# scheda_progetto_ver_4_2.net
KiCad netlist of a schematic drawn in EAGLE
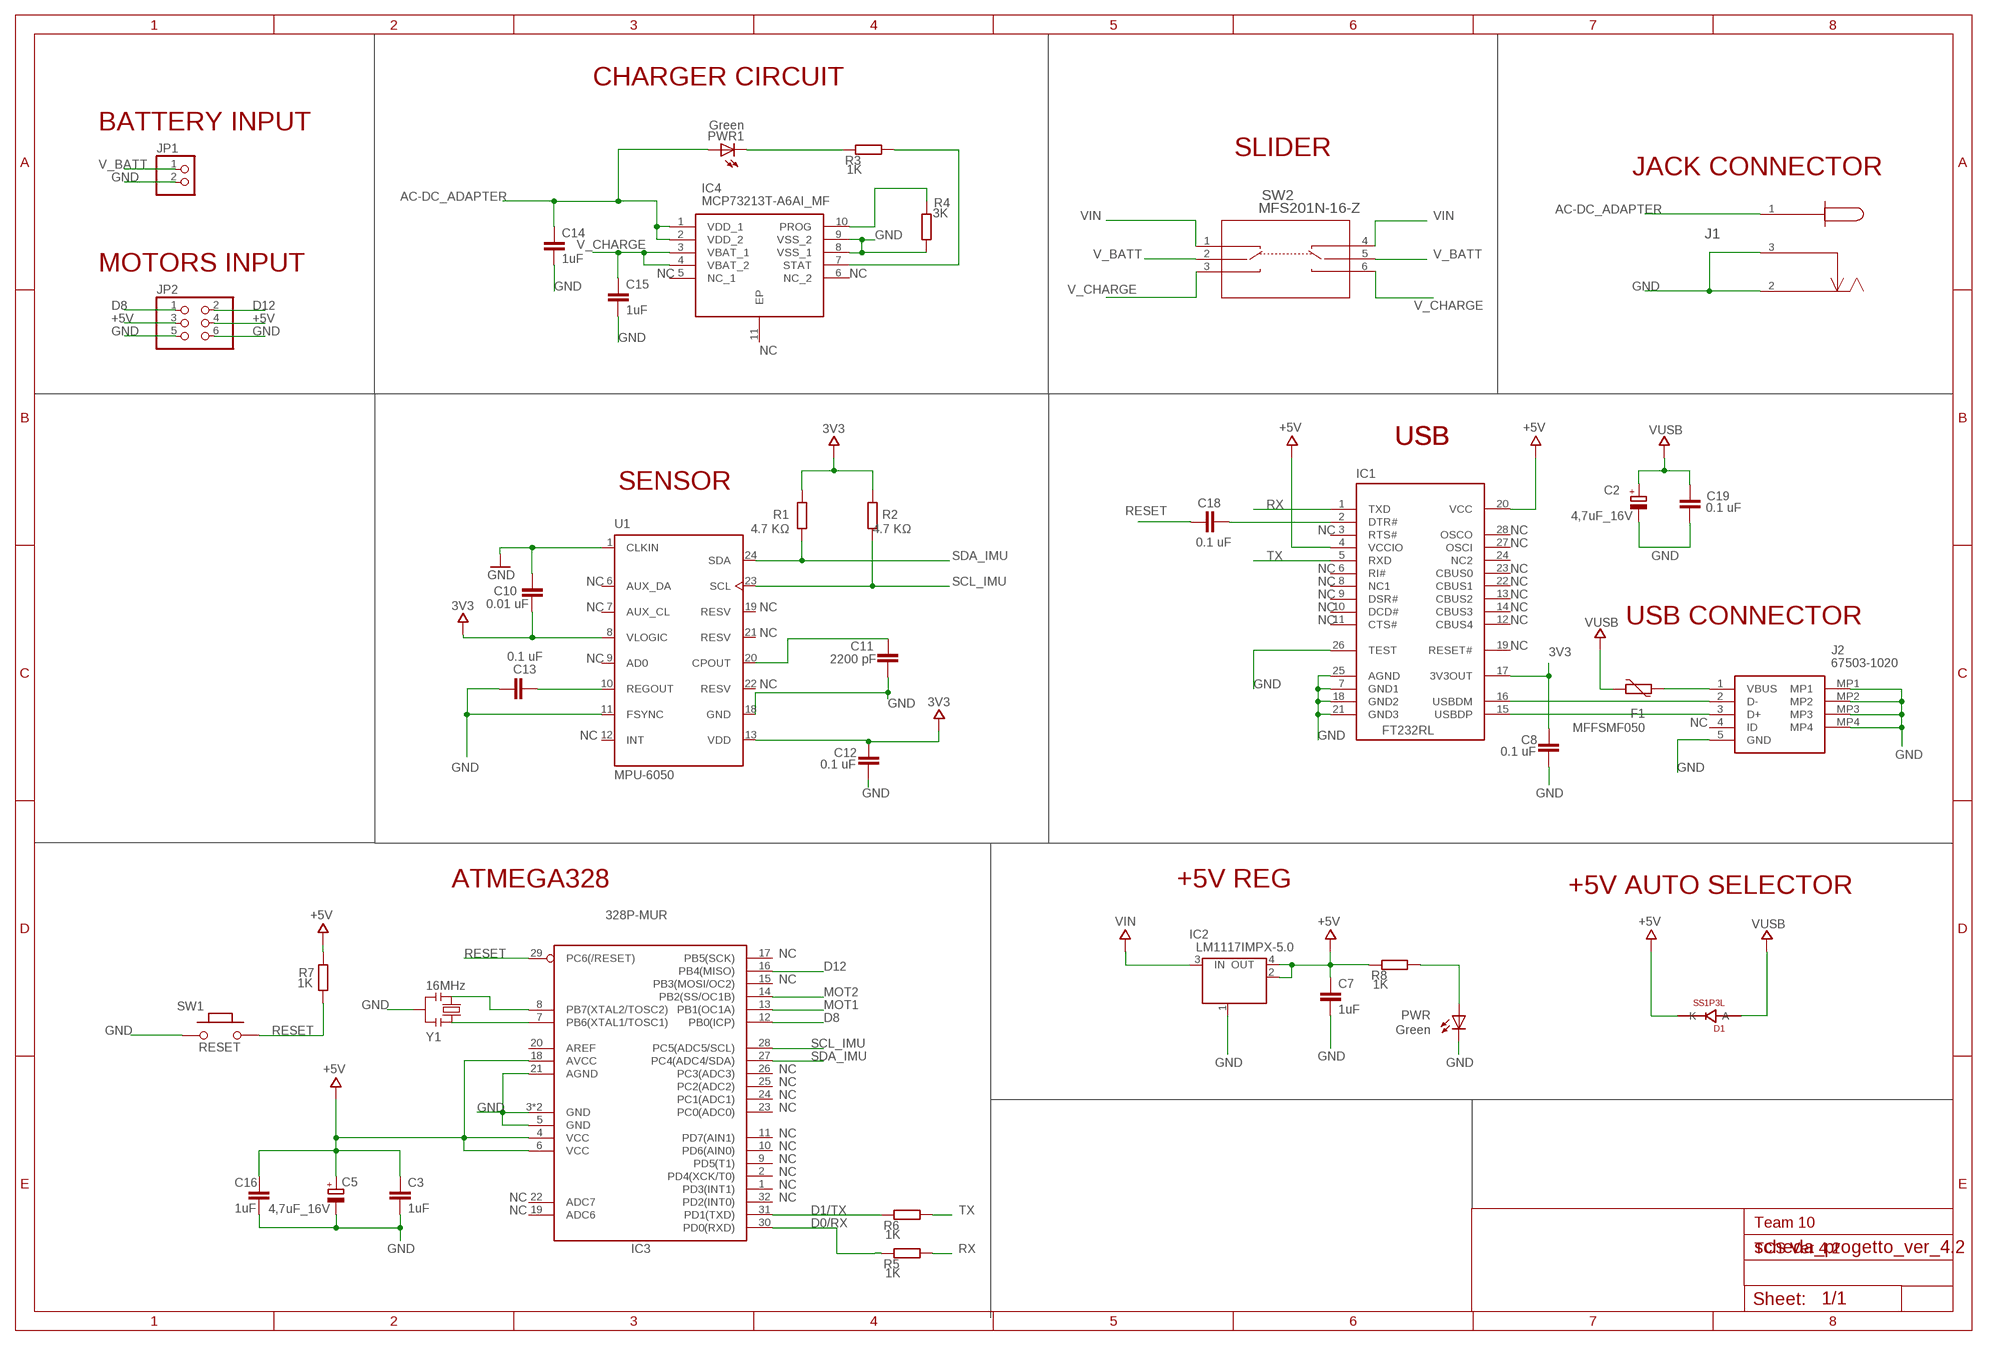
[diagram p0: schematic, sheet 1]

(export (version "E")
  (design (tool "Eeschema 10.0.6"))
  (components
    (comp (ref "C2")
      (value "4,7uF_16V")
      (footprint "eagle-import:TAN-A")
      (fields
        (field (name "PART_NUMBER") "TAJA475MO16RNJ")
        (field (name "MF") "KYOCERA AVX")
        (field (name "MPN") "TAJA475M016RNJ")
      )
      (libsource (lib "eagle-import") (part "0833_TAJA475MO16RNJ"))
    )
    (comp (ref "C3")
      (value "1uF")
      (footprint "eagle-import:C0603")
      (fields (field (name "MF") "KYOCERA AVX") (field (name "MPN") "0603YC105KAT4A"))
      (libsource (lib "eagle-import") (part "C-EUC0603"))
    )
    (comp (ref "C5")
      (value "4,7uF_16V")
      (footprint "eagle-import:TAN-A")
      (fields
        (field (name "PART_NUMBER") "TAJA475MO16RNJ")
        (field (name "MF") "KYOCERA AVX")
        (field (name "MPN") "TAJA475M016RNJ")
      )
      (libsource (lib "eagle-import") (part "0833_TAJA475MO16RNJ"))
    )
    (comp (ref "C7")
      (value "1uF")
      (footprint "eagle-import:C0603")
      (fields (field (name "MF") "KYOCERA AVX") (field (name "MPN") "0603YC105KAT4A"))
      (libsource (lib "eagle-import") (part "C-EUC0603"))
    )
    (comp (ref "C8")
      (value "0.1 uF")
      (footprint "eagle-import:C0603")
      (fields (field (name "MF") "KEMET") (field (name "MPN") "C0603C104K3RECTU"))
      (libsource (lib "eagle-import") (part "C-EUC0603"))
    )
    (comp (ref "C10")
      (value "0.01 uF")
      (footprint "eagle-import:C0603")
      (fields (field (name "MF") "MURATA") (field (name "MPN") "GRM1885C1H103JA01D"))
      (libsource (lib "eagle-import") (part "C-EUC0603"))
    )
    (comp (ref "C11")
      (value "2200 pF")
      (footprint "eagle-import:C0603")
      (fields (field (name "MF") "WURTH ELEKTRONIK") (field (name "MPN") "885012206061"))
      (libsource (lib "eagle-import") (part "C-EUC0603"))
    )
    (comp (ref "C12")
      (value "0.1 uF")
      (footprint "eagle-import:C0603")
      (fields (field (name "MF") "KEMET") (field (name "MPN") "C0603C104K3RECTU"))
      (libsource (lib "eagle-import") (part "C-EUC0603"))
    )
    (comp (ref "C13")
      (value "0.1 uF")
      (footprint "eagle-import:C0603")
      (fields (field (name "MF") "KEMET") (field (name "MPN") "C0603C104K3RECTU"))
      (libsource (lib "eagle-import") (part "C-EUC0603"))
    )
    (comp (ref "C14")
      (value "1uF")
      (footprint "eagle-import:C0603")
      (fields (field (name "MF") "KYOCERA AVX") (field (name "MPN") "0603YC105KAT4A"))
      (libsource (lib "eagle-import") (part "C-EUC0603"))
    )
    (comp (ref "C15")
      (value "1uF")
      (footprint "eagle-import:C0603")
      (fields (field (name "MF") "KYOCERA AVX") (field (name "MPN") "0603YC105KAT4A"))
      (libsource (lib "eagle-import") (part "C-EUC0603"))
    )
    (comp (ref "C16")
      (value "1uF")
      (footprint "eagle-import:C0603")
      (fields (field (name "MF") "KYOCERA AVX") (field (name "MPN") "0603YC105KAT4A"))
      (libsource (lib "eagle-import") (part "C-EUC0603"))
    )
    (comp (ref "C18")
      (value "0.1 uF")
      (footprint "eagle-import:C0603")
      (fields (field (name "MF") "KEMET") (field (name "MPN") "C0603C104K3RECTU"))
      (libsource (lib "eagle-import") (part "C-EUC0603"))
    )
    (comp (ref "C19")
      (value "0.1 uF")
      (footprint "eagle-import:C0603")
      (fields (field (name "MF") "KEMET") (field (name "MPN") "C0603C104K3RECTU"))
      (libsource (lib "eagle-import") (part "C-EUC0603"))
    )
    (comp (ref "D1")
      (value "SS1P3L")
      (footprint "eagle-import:DO220AAL")
      (fields (field (name "PART_NUMBER") "SS1P3L-M3/84A") (field (name "MF") "VISHAY"))
      (libsource (lib "eagle-import") (part "0025_SS1P3L-M3/84A"))
    )
    (comp (ref "F1")
      (value "MFFSMF050")
      (footprint "eagle-import:0603-1608X90N")
      (fields
        (field (name "MANUFACTURER") "Bourns Inc ")
        (field (name "MF") "BOURNS")
        (field (name "MPN") "MF-FSMF050X-2")
      )
      (libsource (lib "eagle-import") (part "PTC"))
    )
    (comp (ref "IC1")
      (value "FT232RL")
      (footprint "eagle-import:SSOP28")
      (libsource (lib "eagle-import") (part "0226_FT232RL"))
    )
    (comp (ref "IC2")
      (value "LM1117IMPX-5.0")
      (footprint "eagle-import:LINEAR_SOT223")
      (libsource (lib "eagle-import") (part "0022_LM1117IMPX-5.0"))
    )
    (comp (ref "IC3")
      (value "328P-MUR")
      (footprint "eagle-import:VQFN32")
      (fields
        (field (name "MANUFACTURER") "ATMEL")
        (field (name "MF") "MICROCHIP")
        (field (name "MPN") "ATMEGA328P-MUR")
      )
      (libsource (lib "eagle-import") (part "ATMEGA328P-32MUR"))
    )
    (comp (ref "IC4")
      (value "MCP73213T-A6AI_MF")
      (footprint "eagle-import:SON50P300X300X100-11N")
      (fields
        (field (name "MANUFACTURER_PART_NUMBER") "MCP73213T-A6AI/MF")
        (field (name "MOUSER_PART_NUMBER") "579-MCP73213TA6AIMF")
      )
      (libsource (lib "eagle-import") (part "MCP73213T-A6AI_MF"))
    )
    (comp (ref "J1")
      (value "694106105102")
      (footprint "eagle-import:CONN3_06105102_WRE")
      (fields
        (field (name "MF") "WURTH ELEKTRONIK")
        (field (name "COPYRIGHT") "Copyright (C) 2023 Ultra Librarian. All rights reserved.")
      )
      (libsource (lib "eagle-import") (part "694106105102"))
    )
    (comp (ref "J2")
      (value "67503-1020")
      (footprint "eagle-import:675031020")
      (fields
        (field (name "MOUSER_PART_NUMBER") "538-67503-1020")
        (field (name "MF") "MOLEX")
        (field (name "MPN") "67503-1020...")
      )
      (libsource (lib "eagle-import") (part "67503-1020"))
    )
    (comp (ref "JP1")
      (value "PINHD-1X2")
      (footprint "eagle-import:1X02")
      (fields (field (name "MF") "AMP - TE CONNECTIVITY") (field (name "MPN") "171826-2"))
      (libsource (lib "eagle-import") (part "PINHD-1X2"))
    )
    (comp (ref "JP2")
      (value "PINHD-2X3")
      (footprint "eagle-import:2X03")
      (fields (field (name "MF") "MOLEX") (field (name "MPN") "87911-0611"))
      (libsource (lib "eagle-import") (part "PINHD-2X3"))
    )
    (comp (ref "PWR")
      (value "Green")
      (footprint "eagle-import:CHIPLED_0805")
      (fields (field (name "PART_NUMBER") "KPT-2012SGC") (field (name "MF") "KINGBRIGHT"))
      (libsource (lib "eagle-import") (part "0043_KPT-2012SGC"))
    )
    (comp (ref "PWR1")
      (value "Green")
      (footprint "eagle-import:CHIPLED_0805")
      (fields (field (name "PART_NUMBER") "KPT-2012SGC") (field (name "MF") "KINGBRIGHT"))
      (libsource (lib "eagle-import") (part "0043_KPT-2012SGC"))
    )
    (comp (ref "R1")
      (value "4.7 KΩ")
      (footprint "eagle-import:R0603")
      (fields (field (name "MF") "YAGEO") (field (name "MPN") "AC0603JR-074K7L"))
      (libsource (lib "eagle-import") (part "R-EU_R0603"))
    )
    (comp (ref "R2")
      (value "4.7 KΩ")
      (footprint "eagle-import:R0603")
      (fields (field (name "MF") "YAGEO") (field (name "MPN") "AC0603JR-074K7L"))
      (libsource (lib "eagle-import") (part "R-EU_R0603"))
    )
    (comp (ref "R3")
      (value "1K")
      (footprint "eagle-import:R0603")
      (fields (field (name "MF") "BOURNS") (field (name "MPN") "CAY16-102J4LF"))
      (libsource (lib "eagle-import") (part "R-EU_R0603"))
    )
    (comp (ref "R4")
      (value "3K")
      (footprint "eagle-import:R0603")
      (fields (field (name "MF") "BOURNS") (field (name "MPN") "CR0603-JW-302ELF"))
      (libsource (lib "eagle-import") (part "R-EU_R0603"))
    )
    (comp (ref "R5")
      (value "1K")
      (footprint "eagle-import:R0603")
      (fields (field (name "MF") "BOURNS") (field (name "MPN") "CAY16-102J4LF"))
      (libsource (lib "eagle-import") (part "R-EU_R0603"))
    )
    (comp (ref "R6")
      (value "1K")
      (footprint "eagle-import:R0603")
      (fields (field (name "MF") "BOURNS") (field (name "MPN") "CAY16-102J4LF"))
      (libsource (lib "eagle-import") (part "R-EU_R0603"))
    )
    (comp (ref "R7")
      (value "1K")
      (footprint "eagle-import:R0603")
      (fields (field (name "MF") "BOURNS") (field (name "MPN") "CAY16-102J4LF"))
      (libsource (lib "eagle-import") (part "R-EU_R0603"))
    )
    (comp (ref "R8")
      (value "1K")
      (footprint "eagle-import:R0603")
      (fields (field (name "MF") "BOURNS") (field (name "MPN") "CAY16-102J4LF"))
      (libsource (lib "eagle-import") (part "R-EU_R0603"))
    )
    (comp (ref "SW1")
      (value "RESET")
      (footprint "eagle-import:SMD_157SW")
      (fields
        (field (name "PART_NUMBER") "IT-1185AP1C-160G-G_T&R")
        (field (name "MF") "MULTICOMP PRO")
        (field (name "MPN") "R13-24AL-05-BB")
      )
      (libsource (lib "eagle-import") (part "0173_IT-1185AP1C-160G-G_T&R"))
    )
    (comp (ref "SW2")
      (value "MFS201N-16-Z")
      (footprint "eagle-import:MFS201N-16-Z_NDC")
      (fields
        (field (name "MF") "NIDEC COMPONENTS")
        (field (name "COPYRIGHT") "Copyright (C) 2023 Ultra Librarian. All rights reserved.")
      )
      (libsource (lib "eagle-import") (part "MFS201N-16-Z"))
    )
    (comp (ref "U1")
      (value "MPU-6050")
      (footprint "eagle-import:QFN50P400X400X95-24N")
      (fields (field (name "MF") "TDK InvenSense") (field (name "MF_1") "TDK INVENSENSE"))
      (libsource (lib "eagle-import") (part "MPU-6050"))
    )
    (comp (ref "Y1")
      (value "16MHz")
      (footprint "eagle-import:RESONATOR")
      (fields (field (name "PART_NUMBER") "CSTCE16M0V53-R0"))
      (libsource (lib "eagle-import") (part "0011_CSTCE16M0V53-R0"))
    )
  )
  (nets
    (net (code "1") (name "+5V") (class "Default")
      (node (ref "C16") (pin "1") (pinfunction "1_1") (pintype "passive"))
      (node (ref "C3") (pin "1") (pinfunction "1_1") (pintype "passive"))
      (node (ref "C5") (pin "1") (pinfunction "+_1") (pintype "passive"))
      (node (ref "C7") (pin "1") (pinfunction "1_1") (pintype "passive"))
      (node (ref "D1") (pin "P$1") (pinfunction "K_P$1") (pintype "bidirectional"))
      (node (ref "IC1") (pin "20") (pinfunction "VCC_20") (pintype "power_in"))
      (node (ref "IC1") (pin "4") (pinfunction "VCCIO_4") (pintype "power_in"))
      (node (ref "IC2") (pin "2") (pinfunction "OUT_2") (pintype "passive"))
      (node (ref "IC2") (pin "4") (pinfunction "OUT_4") (pintype "passive"))
      (node (ref "IC3") (pin "18") (pinfunction "AVCC_18") (pintype "bidirectional"))
      (node (ref "IC3") (pin "4") (pinfunction "VCC_4") (pintype "bidirectional"))
      (node (ref "IC3") (pin "6") (pinfunction "VCC_6") (pintype "bidirectional"))
      (node (ref "JP2") (pin "3") (pinfunction "3_3") (pintype "passive"))
      (node (ref "JP2") (pin "4") (pinfunction "4_4") (pintype "passive"))
      (node (ref "R7") (pin "2") (pinfunction "2_2") (pintype "passive"))
      (node (ref "R8") (pin "1") (pinfunction "1_1") (pintype "passive"))
    )
    (net (code "2") (name "/AC-DC_ADAPTER") (class "Default")
      (node (ref "C14") (pin "1") (pinfunction "1_1") (pintype "passive"))
      (node (ref "IC4") (pin "1") (pinfunction "VDD_1_1") (pintype "bidirectional"))
      (node (ref "IC4") (pin "2") (pinfunction "VDD_2_2") (pintype "bidirectional"))
      (node (ref "J1") (pin "1") (pinfunction "1_1") (pintype "passive"))
      (node (ref "PWR1") (pin "A") (pinfunction "A_A") (pintype "passive"))
    )
    (net (code "3") (name "/D0{slash}RX") (class "Default")
      (node (ref "IC3") (pin "30") (pinfunction "PD0(RXD)_30") (pintype "bidirectional"))
      (node (ref "R5") (pin "1") (pinfunction "1_1") (pintype "passive"))
    )
    (net (code "4") (name "/D1{slash}TX") (class "Default")
      (node (ref "IC3") (pin "31") (pinfunction "PD1(TXD)_31") (pintype "bidirectional"))
      (node (ref "R6") (pin "1") (pinfunction "1_1") (pintype "passive"))
    )
    (net (code "5") (name "/D8") (class "Default")
      (node (ref "IC3") (pin "12") (pinfunction "PB0(ICP)_12") (pintype "bidirectional"))
      (node (ref "JP2") (pin "1") (pinfunction "1_1") (pintype "passive"))
    )
    (net (code "6") (name "/D12") (class "Default")
      (node (ref "IC3") (pin "16") (pinfunction "PB4(MISO)_16") (pintype "bidirectional"))
      (node (ref "JP2") (pin "2") (pinfunction "2_2") (pintype "passive"))
    )
    (net (code "7") (name "/MOT1") (class "Default")
      (node (ref "IC3") (pin "13") (pinfunction "PB1(OC1A)_13") (pintype "bidirectional"))
    )
    (net (code "8") (name "/MOT2") (class "Default")
      (node (ref "IC3") (pin "14") (pinfunction "PB2(SS/OC1B)_14") (pintype "bidirectional"))
    )
    (net (code "9") (name "/RESET") (class "Default")
      (node (ref "C18") (pin "2") (pinfunction "2_2") (pintype "passive"))
      (node (ref "IC3") (pin "29") (pinfunction "PC6(/RESET)_29") (pintype "bidirectional"))
      (node (ref "R7") (pin "1") (pinfunction "1_1") (pintype "passive"))
      (node (ref "SW1") (pin "2") (pinfunction "2_2") (pintype "passive"))
    )
    (net (code "10") (name "/RX") (class "Default")
      (node (ref "IC1") (pin "1") (pinfunction "TXD_1") (pintype "output"))
      (node (ref "R5") (pin "2") (pinfunction "2_2") (pintype "passive"))
    )
    (net (code "11") (name "/SCL_IMU") (class "Default")
      (node (ref "IC3") (pin "28") (pinfunction "PC5(ADC5/SCL)_28") (pintype "bidirectional"))
      (node (ref "R2") (pin "1") (pinfunction "1_1") (pintype "passive"))
      (node (ref "U1") (pin "23") (pinfunction "SCL_23") (pintype "input"))
    )
    (net (code "12") (name "/SDA_IMU") (class "Default")
      (node (ref "IC3") (pin "27") (pinfunction "PC4(ADC4/SDA)_27") (pintype "bidirectional"))
      (node (ref "R1") (pin "1") (pinfunction "1_1") (pintype "passive"))
      (node (ref "U1") (pin "24") (pinfunction "SDA_24") (pintype "bidirectional"))
    )
    (net (code "13") (name "/TX") (class "Default")
      (node (ref "IC1") (pin "5") (pinfunction "RXD_5") (pintype "input"))
      (node (ref "R6") (pin "2") (pinfunction "2_2") (pintype "passive"))
    )
    (net (code "14") (name "/V_BATT") (class "Default")
      (node (ref "JP1") (pin "1") (pinfunction "1_1") (pintype "passive"))
      (node (ref "SW2") (pin "2") (pinfunction "2_2") (pintype "passive"))
      (node (ref "SW2") (pin "5") (pinfunction "5_5") (pintype "passive"))
    )
    (net (code "15") (name "/V_CHARGE") (class "Default")
      (node (ref "C15") (pin "1") (pinfunction "1_1") (pintype "passive"))
      (node (ref "IC4") (pin "3") (pinfunction "VBAT_1_3") (pintype "bidirectional"))
      (node (ref "IC4") (pin "4") (pinfunction "VBAT_2_4") (pintype "bidirectional"))
      (node (ref "SW2") (pin "3") (pinfunction "3_3") (pintype "passive"))
      (node (ref "SW2") (pin "6") (pinfunction "6_6") (pintype "passive"))
    )
    (net (code "16") (name "3V3") (class "Default")
      (node (ref "C10") (pin "1") (pinfunction "1_1") (pintype "passive"))
      (node (ref "C12") (pin "2") (pinfunction "2_2") (pintype "passive"))
      (node (ref "C8") (pin "2") (pinfunction "2_2") (pintype "passive"))
      (node (ref "IC1") (pin "17") (pinfunction "3V3OUT_17") (pintype "power_in"))
      (node (ref "R1") (pin "2") (pinfunction "2_2") (pintype "passive"))
      (node (ref "R2") (pin "2") (pinfunction "2_2") (pintype "passive"))
      (node (ref "U1") (pin "13") (pinfunction "VDD_13") (pintype "power_in"))
      (node (ref "U1") (pin "8") (pinfunction "VLOGIC_8") (pintype "power_in"))
    )
    (net (code "17") (name "GND") (class "Default")
      (node (ref "C10") (pin "2") (pinfunction "2_2") (pintype "passive"))
      (node (ref "C11") (pin "1") (pinfunction "1_1") (pintype "passive"))
      (node (ref "C12") (pin "1") (pinfunction "1_1") (pintype "passive"))
      (node (ref "C13") (pin "2") (pinfunction "2_2") (pintype "passive"))
      (node (ref "C14") (pin "2") (pinfunction "2_2") (pintype "passive"))
      (node (ref "C15") (pin "2") (pinfunction "2_2") (pintype "passive"))
      (node (ref "C16") (pin "2") (pinfunction "2_2") (pintype "passive"))
      (node (ref "C19") (pin "1") (pinfunction "1_1") (pintype "passive"))
      (node (ref "C2") (pin "2") (pinfunction "-_2") (pintype "passive"))
      (node (ref "C3") (pin "2") (pinfunction "2_2") (pintype "passive"))
      (node (ref "C5") (pin "2") (pinfunction "-_2") (pintype "passive"))
      (node (ref "C7") (pin "2") (pinfunction "2_2") (pintype "passive"))
      (node (ref "C8") (pin "1") (pinfunction "1_1") (pintype "passive"))
      (node (ref "IC1") (pin "18") (pinfunction "GND2_18") (pintype "power_in"))
      (node (ref "IC1") (pin "21") (pinfunction "GND3_21") (pintype "power_in"))
      (node (ref "IC1") (pin "25") (pinfunction "AGND_25") (pintype "power_in"))
      (node (ref "IC1") (pin "26") (pinfunction "TEST_26") (pintype "bidirectional"))
      (node (ref "IC1") (pin "7") (pinfunction "GND1_7") (pintype "power_in"))
      (node (ref "IC2") (pin "1") (pinfunction "GND/ADJ_1") (pintype "input"))
      (node (ref "IC3") (pin "21") (pinfunction "AGND_21") (pintype "bidirectional"))
      (node (ref "IC3") (pin "3") (pinfunction "GND_3") (pintype "bidirectional"))
      (node (ref "IC3") (pin "33") (pinfunction "GND_33") (pintype "bidirectional"))
      (node (ref "IC3") (pin "5") (pinfunction "GND_5") (pintype "bidirectional"))
      (node (ref "IC4") (pin "8") (pinfunction "VSS_1_8") (pintype "bidirectional"))
      (node (ref "IC4") (pin "9") (pinfunction "VSS_2_9") (pintype "bidirectional"))
      (node (ref "J1") (pin "2") (pinfunction "2_2") (pintype "passive"))
      (node (ref "J1") (pin "3") (pinfunction "3_3") (pintype "passive"))
      (node (ref "J2") (pin "5") (pinfunction "GND_5") (pintype "bidirectional"))
      (node (ref "J2") (pin "MP1") (pinfunction "MP1_MP1") (pintype "bidirectional"))
      (node (ref "J2") (pin "MP2") (pinfunction "MP2_MP2") (pintype "bidirectional"))
      (node (ref "J2") (pin "MP3") (pinfunction "MP3_MP3") (pintype "bidirectional"))
      (node (ref "J2") (pin "MP4") (pinfunction "MP4_MP4") (pintype "bidirectional"))
      (node (ref "JP1") (pin "2") (pinfunction "2_2") (pintype "passive"))
      (node (ref "JP2") (pin "5") (pinfunction "5_5") (pintype "passive"))
      (node (ref "JP2") (pin "6") (pinfunction "6_6") (pintype "passive"))
      (node (ref "PWR") (pin "C") (pinfunction "C_C") (pintype "passive"))
      (node (ref "R4") (pin "2") (pinfunction "2_2") (pintype "passive"))
      (node (ref "SW1") (pin "1") (pinfunction "1_1") (pintype "passive"))
      (node (ref "U1") (pin "1") (pinfunction "CLKIN_1") (pintype "input"))
      (node (ref "U1") (pin "11") (pinfunction "FSYNC_11") (pintype "input"))
      (node (ref "U1") (pin "18") (pinfunction "GND_18") (pintype "power_in"))
      (node (ref "Y1") (pin "2") (pinfunction "2_2") (pintype "passive"))
    )
    (net (code "18") (name "Net-(IC1-DTR#)") (class "Default")
      (node (ref "C18") (pin "1") (pinfunction "1_1") (pintype "passive"))
      (node (ref "IC1") (pin "2") (pinfunction "DTR#_2") (pintype "output"))
    )
    (net (code "19") (name "Net-(IC1-USBDM)") (class "Default")
      (node (ref "IC1") (pin "16") (pinfunction "USBDM_16") (pintype "bidirectional"))
      (node (ref "J2") (pin "2") (pinfunction "D-_2") (pintype "bidirectional"))
    )
    (net (code "20") (name "Net-(IC1-USBDP)") (class "Default")
      (node (ref "IC1") (pin "15") (pinfunction "USBDP_15") (pintype "bidirectional"))
      (node (ref "J2") (pin "3") (pinfunction "D+_3") (pintype "bidirectional"))
    )
    (net (code "21") (name "Net-(IC3-PB6(XTAL1{slash}TOSC1))") (class "Default")
      (node (ref "IC3") (pin "7") (pinfunction "PB6(XTAL1/TOSC1)_7") (pintype "bidirectional"))
      (node (ref "Y1") (pin "1") (pinfunction "1_1") (pintype "passive"))
    )
    (net (code "22") (name "Net-(IC3-PB7(XTAL2{slash}TOSC2))") (class "Default")
      (node (ref "IC3") (pin "8") (pinfunction "PB7(XTAL2/TOSC2)_8") (pintype "bidirectional"))
      (node (ref "Y1") (pin "3") (pinfunction "3_3") (pintype "passive"))
    )
    (net (code "23") (name "Net-(IC4-PROG)") (class "Default")
      (node (ref "IC4") (pin "10") (pinfunction "PROG_10") (pintype "bidirectional"))
      (node (ref "R4") (pin "1") (pinfunction "1_1") (pintype "passive"))
    )
    (net (code "24") (name "Net-(IC4-STAT)") (class "Default")
      (node (ref "IC4") (pin "7") (pinfunction "STAT_7") (pintype "bidirectional"))
      (node (ref "R3") (pin "2") (pinfunction "2_2") (pintype "passive"))
    )
    (net (code "25") (name "Net-(J2-VBUS)") (class "Default")
      (node (ref "F1") (pin "2") (pinfunction "2_2") (pintype "passive"))
      (node (ref "J2") (pin "1") (pinfunction "VBUS_1") (pintype "bidirectional"))
    )
    (net (code "26") (name "Net-(PWR-PadA)") (class "Default")
      (node (ref "PWR") (pin "A") (pinfunction "A_A") (pintype "passive"))
      (node (ref "R8") (pin "2") (pinfunction "2_2") (pintype "passive"))
    )
    (net (code "27") (name "Net-(PWR1-PadC)") (class "Default")
      (node (ref "PWR1") (pin "C") (pinfunction "C_C") (pintype "passive"))
      (node (ref "R3") (pin "1") (pinfunction "1_1") (pintype "passive"))
    )
    (net (code "28") (name "Net-(U1-CPOUT)") (class "Default")
      (node (ref "C11") (pin "2") (pinfunction "2_2") (pintype "passive"))
      (node (ref "U1") (pin "20") (pinfunction "CPOUT_20") (pintype "passive"))
    )
    (net (code "29") (name "Net-(U1-REGOUT)") (class "Default")
      (node (ref "C13") (pin "1") (pinfunction "1_1") (pintype "passive"))
      (node (ref "U1") (pin "10") (pinfunction "REGOUT_10") (pintype "passive"))
    )
    (net (code "30") (name "VIN") (class "Default")
      (node (ref "IC2") (pin "3") (pinfunction "IN_3") (pintype "input"))
      (node (ref "SW2") (pin "1") (pinfunction "1_1") (pintype "passive"))
      (node (ref "SW2") (pin "4") (pinfunction "4_4") (pintype "passive"))
    )
    (net (code "31") (name "VUSB") (class "Default")
      (node (ref "C19") (pin "2") (pinfunction "2_2") (pintype "passive"))
      (node (ref "C2") (pin "1") (pinfunction "+_1") (pintype "passive"))
      (node (ref "D1") (pin "P$2") (pinfunction "A_P$2") (pintype "bidirectional"))
      (node (ref "F1") (pin "1") (pinfunction "1_1") (pintype "passive"))
    )
    (net (code "32") (name "unconnected-(IC1-CBUS0-Pad23)") (class "Default")
      (node (ref "IC1") (pin "23") (pinfunction "CBUS0_23") (pintype "bidirectional"))
    )
    (net (code "33") (name "unconnected-(IC1-CBUS1-Pad22)") (class "Default")
      (node (ref "IC1") (pin "22") (pinfunction "CBUS1_22") (pintype "bidirectional"))
    )
    (net (code "34") (name "unconnected-(IC1-CBUS2-Pad13)") (class "Default")
      (node (ref "IC1") (pin "13") (pinfunction "CBUS2_13") (pintype "bidirectional"))
    )
    (net (code "35") (name "unconnected-(IC1-CBUS3-Pad14)") (class "Default")
      (node (ref "IC1") (pin "14") (pinfunction "CBUS3_14") (pintype "bidirectional"))
    )
    (net (code "36") (name "unconnected-(IC1-CBUS4-Pad12)") (class "Default")
      (node (ref "IC1") (pin "12") (pinfunction "CBUS4_12") (pintype "bidirectional"))
    )
    (net (code "37") (name "unconnected-(IC1-CTS#-Pad11)") (class "Default")
      (node (ref "IC1") (pin "11") (pinfunction "CTS#_11") (pintype "bidirectional"))
    )
    (net (code "38") (name "unconnected-(IC1-DCD#-Pad10)") (class "Default")
      (node (ref "IC1") (pin "10") (pinfunction "DCD#_10") (pintype "bidirectional"))
    )
    (net (code "39") (name "unconnected-(IC1-DSR#-Pad9)") (class "Default")
      (node (ref "IC1") (pin "9") (pinfunction "DSR#_9") (pintype "bidirectional"))
    )
    (net (code "40") (name "unconnected-(IC1-NC1-Pad8)") (class "Default")
      (node (ref "IC1") (pin "8") (pinfunction "NC1_8") (pintype "bidirectional"))
    )
    (net (code "41") (name "unconnected-(IC1-NC2-Pad24)") (class "Default")
      (node (ref "IC1") (pin "24") (pinfunction "NC2_24") (pintype "no_connect"))
    )
    (net (code "42") (name "unconnected-(IC1-OSCI-Pad27)") (class "Default")
      (node (ref "IC1") (pin "27") (pinfunction "OSCI_27") (pintype "bidirectional"))
    )
    (net (code "43") (name "unconnected-(IC1-OSCO-Pad28)") (class "Default")
      (node (ref "IC1") (pin "28") (pinfunction "OSCO_28") (pintype "output"))
    )
    (net (code "44") (name "unconnected-(IC1-RESET#-Pad19)") (class "Default")
      (node (ref "IC1") (pin "19") (pinfunction "RESET#_19") (pintype "bidirectional"))
    )
    (net (code "45") (name "unconnected-(IC1-RI#-Pad6)") (class "Default")
      (node (ref "IC1") (pin "6") (pinfunction "RI#_6") (pintype "bidirectional"))
    )
    (net (code "46") (name "unconnected-(IC1-RTS#-Pad3)") (class "Default")
      (node (ref "IC1") (pin "3") (pinfunction "RTS#_3") (pintype "output"))
    )
    (net (code "47") (name "unconnected-(IC3-ADC6-Pad19)") (class "Default")
      (node (ref "IC3") (pin "19") (pinfunction "ADC6_19") (pintype "bidirectional"))
    )
    (net (code "48") (name "unconnected-(IC3-ADC7-Pad22)") (class "Default")
      (node (ref "IC3") (pin "22") (pinfunction "ADC7_22") (pintype "bidirectional"))
    )
    (net (code "49") (name "unconnected-(IC3-AREF-Pad20)") (class "Default")
      (node (ref "IC3") (pin "20") (pinfunction "AREF_20") (pintype "bidirectional"))
    )
    (net (code "50") (name "unconnected-(IC3-PB3(MOSI{slash}OC2)-Pad15)") (class "Default")
      (node (ref "IC3") (pin "15") (pinfunction "PB3(MOSI/OC2)_15") (pintype "bidirectional"))
    )
    (net (code "51") (name "unconnected-(IC3-PB5(SCK)-Pad17)") (class "Default")
      (node (ref "IC3") (pin "17") (pinfunction "PB5(SCK)_17") (pintype "bidirectional"))
    )
    (net (code "52") (name "unconnected-(IC3-PC0(ADC0)-Pad23)") (class "Default")
      (node (ref "IC3") (pin "23") (pinfunction "PC0(ADC0)_23") (pintype "bidirectional"))
    )
    (net (code "53") (name "unconnected-(IC3-PC1(ADC1)-Pad24)") (class "Default")
      (node (ref "IC3") (pin "24") (pinfunction "PC1(ADC1)_24") (pintype "bidirectional"))
    )
    (net (code "54") (name "unconnected-(IC3-PC2(ADC2)-Pad25)") (class "Default")
      (node (ref "IC3") (pin "25") (pinfunction "PC2(ADC2)_25") (pintype "bidirectional"))
    )
    (net (code "55") (name "unconnected-(IC3-PC3(ADC3)-Pad26)") (class "Default")
      (node (ref "IC3") (pin "26") (pinfunction "PC3(ADC3)_26") (pintype "bidirectional"))
    )
    (net (code "56") (name "unconnected-(IC3-PD2(INT0)-Pad32)") (class "Default")
      (node (ref "IC3") (pin "32") (pinfunction "PD2(INT0)_32") (pintype "bidirectional"))
    )
    (net (code "57") (name "unconnected-(IC3-PD3(INT1)-Pad1)") (class "Default")
      (node (ref "IC3") (pin "1") (pinfunction "PD3(INT1)_1") (pintype "bidirectional"))
    )
    (net (code "58") (name "unconnected-(IC3-PD4(XCK{slash}T0)-Pad2)") (class "Default")
      (node (ref "IC3") (pin "2") (pinfunction "PD4(XCK/T0)_2") (pintype "bidirectional"))
    )
    (net (code "59") (name "unconnected-(IC3-PD5(T1)-Pad9)") (class "Default")
      (node (ref "IC3") (pin "9") (pinfunction "PD5(T1)_9") (pintype "bidirectional"))
    )
    (net (code "60") (name "unconnected-(IC3-PD6(AIN0)-Pad10)") (class "Default")
      (node (ref "IC3") (pin "10") (pinfunction "PD6(AIN0)_10") (pintype "bidirectional"))
    )
    (net (code "61") (name "unconnected-(IC3-PD7(AIN1)-Pad11)") (class "Default")
      (node (ref "IC3") (pin "11") (pinfunction "PD7(AIN1)_11") (pintype "bidirectional"))
    )
    (net (code "62") (name "unconnected-(IC4-EP-Pad11)") (class "Default")
      (node (ref "IC4") (pin "11") (pinfunction "EP_11") (pintype "bidirectional"))
    )
    (net (code "63") (name "unconnected-(IC4-NC_1-Pad5)") (class "Default")
      (node (ref "IC4") (pin "5") (pinfunction "NC_1_5") (pintype "bidirectional"))
    )
    (net (code "64") (name "unconnected-(IC4-NC_2-Pad6)") (class "Default")
      (node (ref "IC4") (pin "6") (pinfunction "NC_2_6") (pintype "bidirectional"))
    )
    (net (code "65") (name "unconnected-(J2-ID-Pad4)") (class "Default")
      (node (ref "J2") (pin "4") (pinfunction "ID_4") (pintype "bidirectional"))
    )
    (net (code "66") (name "unconnected-(U1-AD0-Pad9)") (class "Default")
      (node (ref "U1") (pin "9") (pinfunction "AD0_9") (pintype "input"))
    )
    (net (code "67") (name "unconnected-(U1-AUX_CL-Pad7)") (class "Default")
      (node (ref "U1") (pin "7") (pinfunction "AUX_CL_7") (pintype "input"))
    )
    (net (code "68") (name "unconnected-(U1-AUX_DA-Pad6)") (class "Default")
      (node (ref "U1") (pin "6") (pinfunction "AUX_DA_6") (pintype "bidirectional"))
    )
    (net (code "69") (name "unconnected-(U1-INT-Pad12)") (class "Default")
      (node (ref "U1") (pin "12") (pinfunction "INT_12") (pintype "output"))
    )
    (net (code "70") (name "unconnected-(U1-RESV-Pad19)") (class "Default")
      (node (ref "U1") (pin "19") (pinfunction "RESV_19") (pintype "passive"))
    )
    (net (code "71") (name "unconnected-(U1-RESV-Pad21)") (class "Default")
      (node (ref "U1") (pin "21") (pinfunction "RESV_21") (pintype "passive"))
    )
    (net (code "72") (name "unconnected-(U1-RESV-Pad22)") (class "Default")
      (node (ref "U1") (pin "22") (pinfunction "RESV_22") (pintype "passive"))
    )
  )
)
